# A-Power.net
KiCad netlist of a schematic drawn in Altium Designer
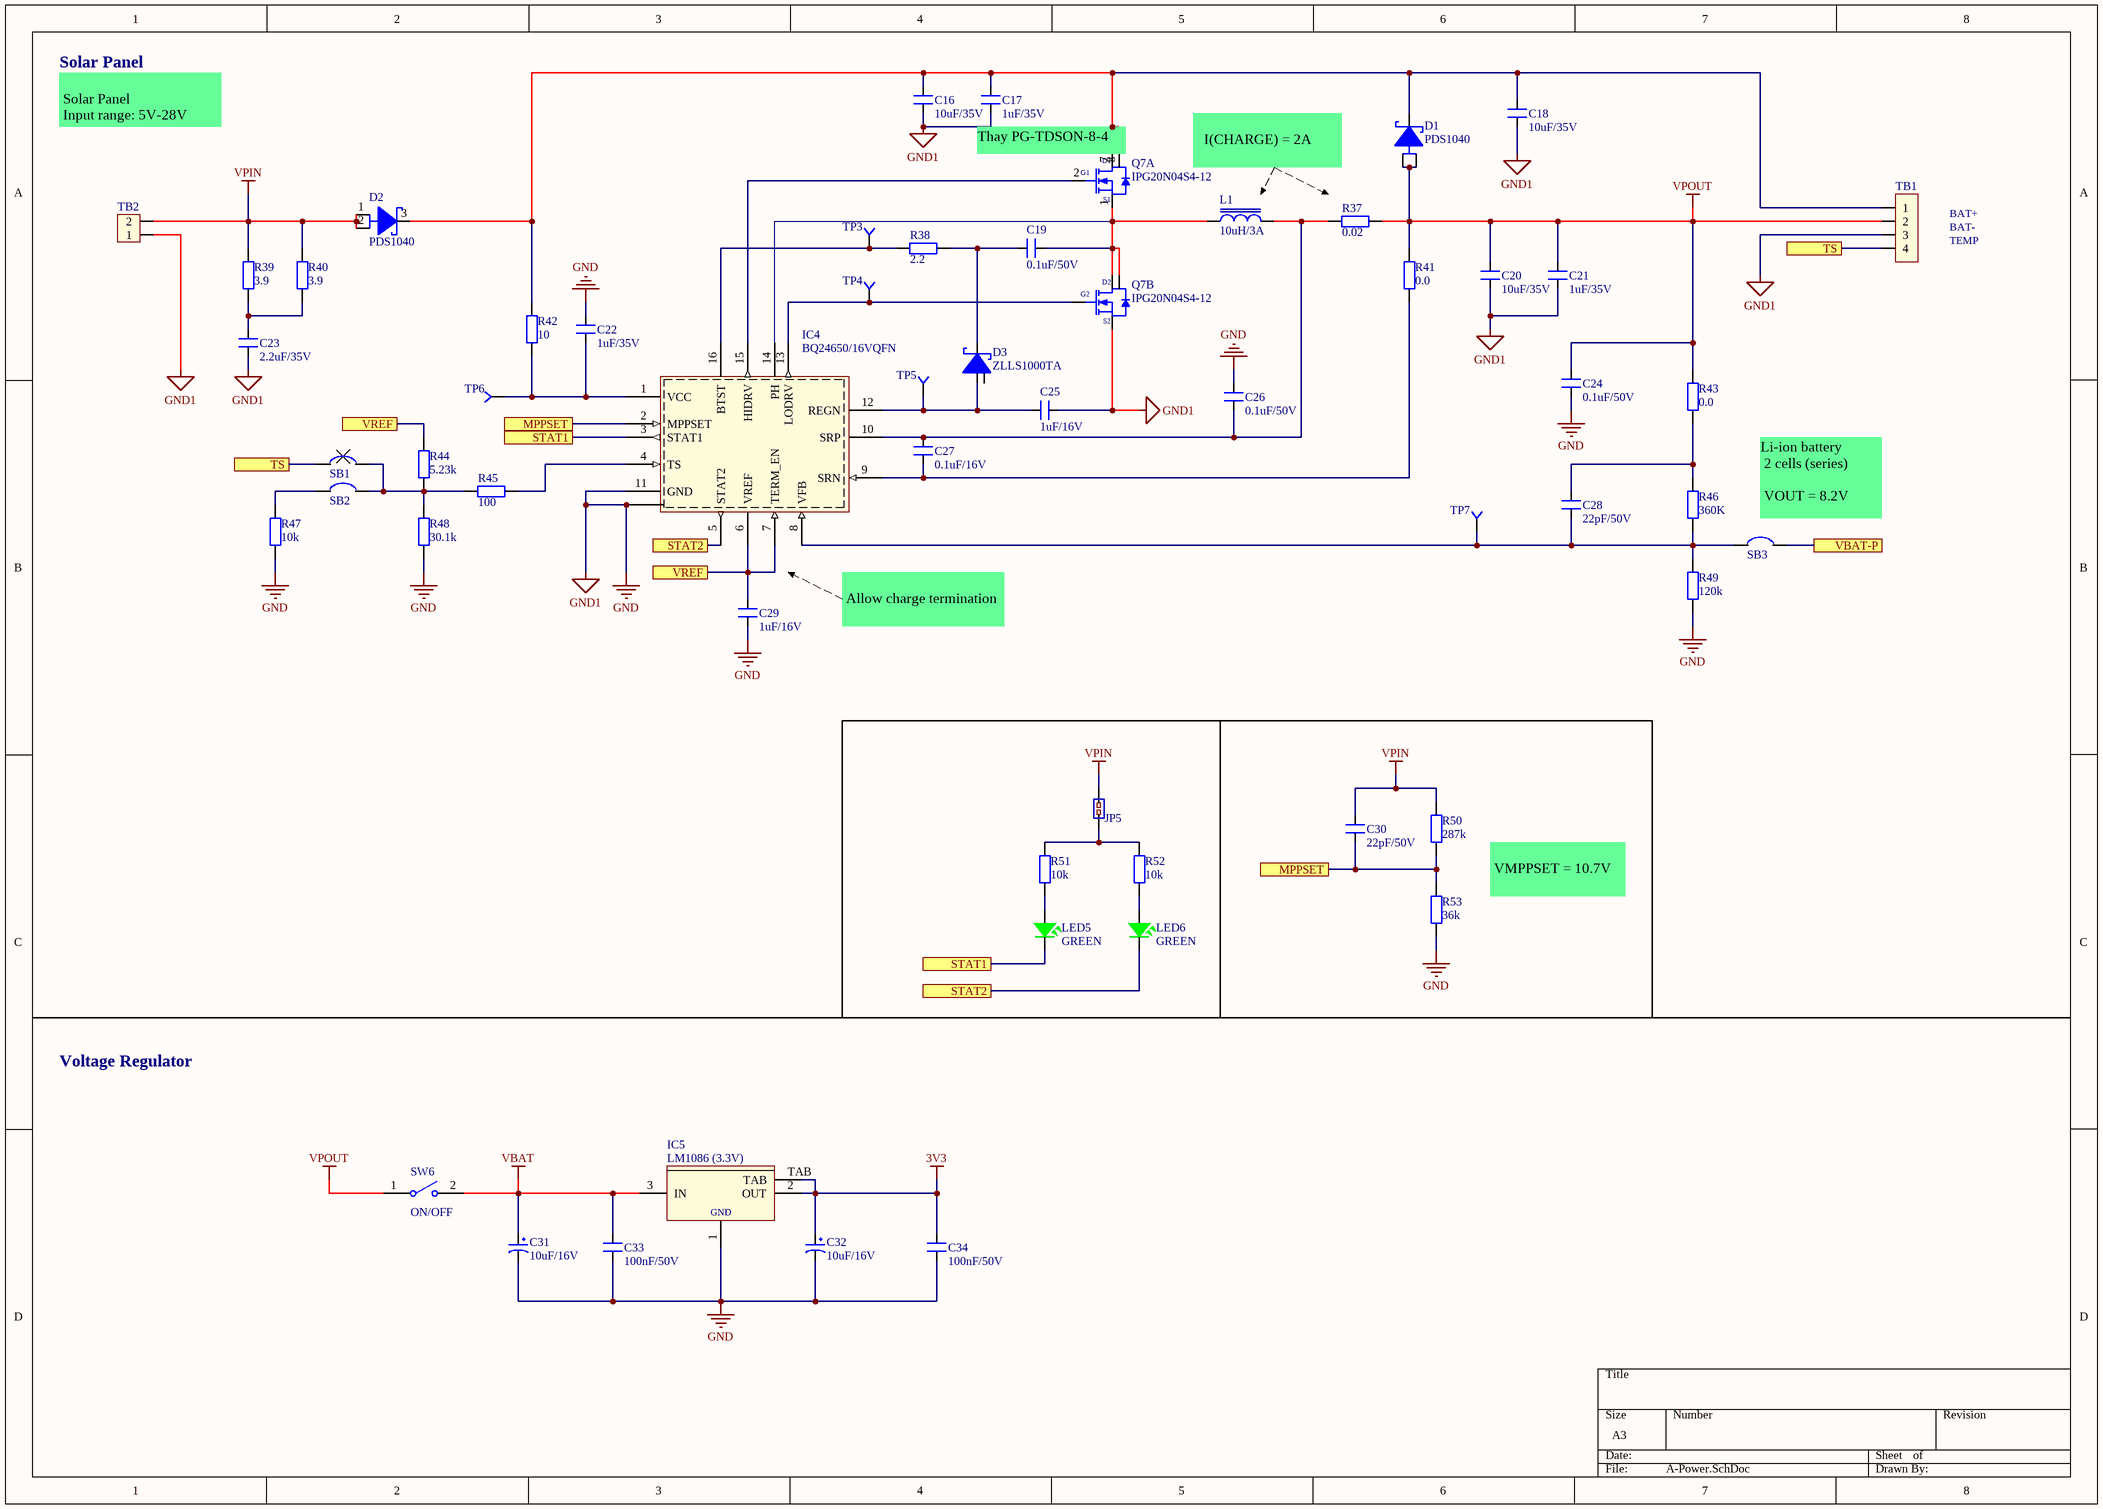
[diagram p0: A-Power.SchDoc]

(export (version "E")
  (design (tool "Eeschema 10.0.6"))
  (components
    (comp (ref "C16")
      (value "10uF/35V")
      (footprint "CAP_CERA_C3216(CC1206INCH)")
      (description "CAP CER 10UF 35V X7R 1206")
      (fields
        (field (name "MANUFACTURER") "Taiyo Yuden")
        (field (name "MANUFACTURER PART NUMBER") "GMK316AB7106KL-TR")
      )
      (libsource (lib "Tran Tuan") (part "CAP-CER/10uF/35V/X7R-1206"))
    )
    (comp (ref "C17")
      (value "1uF/35V")
      (footprint "CAP_CERA_C2012(CC0805INCH)")
      (description "CAP CER 1UF 35V X7R 0805")
      (fields
        (field (name "MANUFACTURER") "Taiyo Yuden")
        (field (name "MANUFACTURER PART NUMBER") "GMK212B7105KG-T")
      )
      (libsource (lib "Tran Tuan") (part "CAP-CER/1uF/35V/X7R/0805"))
    )
    (comp (ref "C18")
      (value "10uF/35V")
      (footprint "CAP_CERA_C3216(CC1206INCH)")
      (description "CAP CER 10UF 35V X7R 1206")
      (fields
        (field (name "MANUFACTURER") "Taiyo Yuden")
        (field (name "MANUFACTURER PART NUMBER") "GMK316AB7106KL-TR")
      )
      (libsource (lib "Tran Tuan") (part "CAP-CER/10uF/35V/X7R-1206"))
    )
    (comp (ref "C19")
      (value "0.1uF/50V")
      (footprint "CAP_CERA_C1608(CC0603INCH)")
      (description "CAP CER 0.1UF 50V X7R 0603")
      (fields
        (field (name "MANUFACTURER") "Kemet")
        (field (name "MANUFACTURER PART NUMBER") "C0603X104K5RACTU")
      )
      (libsource (lib "Tran Tuan") (part "CAP-CER/0.1uF/50V/X7R/0603"))
    )
    (comp (ref "C20")
      (value "10uF/35V")
      (footprint "CAP_CERA_C3216(CC1206INCH)")
      (description "CAP CER 10UF 35V X7R 1206")
      (fields
        (field (name "MANUFACTURER") "Taiyo Yuden")
        (field (name "MANUFACTURER PART NUMBER") "GMK316AB7106KL-TR")
      )
      (libsource (lib "Tran Tuan") (part "CAP-CER/10uF/35V/X7R-1206"))
    )
    (comp (ref "C21")
      (value "1uF/35V")
      (footprint "CAP_CERA_C2012(CC0805INCH)")
      (description "CAP CER 1UF 35V X7R 0805")
      (fields
        (field (name "MANUFACTURER") "Taiyo Yuden")
        (field (name "MANUFACTURER PART NUMBER") "GMK212B7105KG-T")
      )
      (libsource (lib "Tran Tuan") (part "CAP-CER/1uF/35V/X7R/0805"))
    )
    (comp (ref "C22")
      (value "1uF/35V")
      (footprint "CAP_CERA_C2012(CC0805INCH)")
      (description "CAP CER 1UF 35V X7R 0805")
      (fields
        (field (name "MANUFACTURER") "Taiyo Yuden")
        (field (name "MANUFACTURER PART NUMBER") "GMK212B7105KG-T")
      )
      (libsource (lib "Tran Tuan") (part "CAP-CER/1uF/35V/X7R/0805"))
    )
    (comp (ref "C23")
      (value "2.2uF/35V")
      (footprint "CAP_CERA_C3225(CC1210)")
      (description "CAP CER 2.2UF 35V X7R 1210")
      (fields
        (field (name "MANUFACTURER") "Taiyo Yuden")
        (field (name "MANUFACTURER PART NUMBER") "GMK325B7225KNHT")
      )
      (libsource (lib "Tran Tuan") (part "CAP-CER/2.2uF/35V/X7R/1210"))
    )
    (comp (ref "C24")
      (value "0.1uF/50V")
      (footprint "CAP_CERA_C1608(CC0603INCH)")
      (description "CAP CER 0.1UF 50V X7R 0603")
      (fields
        (field (name "MANUFACTURER") "Kemet")
        (field (name "MANUFACTURER PART NUMBER") "C0603X104K5RACTU")
      )
      (libsource (lib "Tran Tuan") (part "CAP-CER/0.1uF/50V/X7R/0603"))
    )
    (comp (ref "C25")
      (value "1uF/16V")
      (footprint "CAP_CERA_C2012(CC0805INCH)")
      (description "CAP CER 1UF 16V X7R 0805")
      (fields
        (field (name "MANUFACTURER") "Kemet")
        (field (name "MANUFACTURER PART NUMBER") "C0805C105K4RACTU")
      )
      (libsource (lib "Tran Tuan") (part "CAP-CER/1uF/16V/X7R/0805"))
    )
    (comp (ref "C26")
      (value "0.1uF/50V")
      (footprint "CAP_CERA_C1608(CC0603INCH)")
      (description "CAP CER 0.1UF 50V X7R 0603")
      (fields
        (field (name "MANUFACTURER") "Kemet")
        (field (name "MANUFACTURER PART NUMBER") "C0603X104K5RACTU")
      )
      (libsource (lib "Tran Tuan") (part "CAP-CER/0.1uF/50V/X7R/0603"))
    )
    (comp (ref "C27")
      (value "0.1uF/16V")
      (footprint "CAP_CERA_C1608(CC0603INCH)")
      (description "CAP CER 0.1UF 16V X7R 0603")
      (fields
        (field (name "MANUFACTURER") "Yageo")
        (field (name "MANUFACTURER PART NUMBER") "CC0603KRX7R7BB104")
      )
      (libsource (lib "Tran Tuan") (part "CAP-CER/0.1uF/16V/X7R/0603"))
    )
    (comp (ref "C28")
      (value "22pF/50V")
      (footprint "CAP_CERA_C1608(CC0603INCH)")
      (description "CAP CER 22PF 50V X7R 0603")
      (fields
        (field (name "MANUFACTURER") "AVX Corporation")
        (field (name "MANUFACTURER PART NUMBER") "06035C220JAT2A")
      )
      (libsource (lib "Tran Tuan") (part "CAP-CER/22pF/50V/X7R/0603"))
    )
    (comp (ref "C29")
      (value "1uF/16V")
      (footprint "CAP_CERA_C2012(CC0805INCH)")
      (description "CAP CER 1UF 16V X7R 0805")
      (fields
        (field (name "MANUFACTURER") "Kemet")
        (field (name "MANUFACTURER PART NUMBER") "C0805C105K4RACTU")
      )
      (libsource (lib "Tran Tuan") (part "CAP-CER/1uF/16V/X7R/0805"))
    )
    (comp (ref "C30")
      (value "22pF/50V")
      (footprint "CAP_CERA_C1608(CC0603INCH)")
      (description "CAP CER 22PF 50V X7R 0603")
      (fields
        (field (name "MANUFACTURER") "AVX Corporation")
        (field (name "MANUFACTURER PART NUMBER") "06035C220JAT2A")
      )
      (libsource (lib "Tran Tuan") (part "CAP-CER/22pF/50V/X7R/0603"))
    )
    (comp (ref "C31")
      (value "10uF/16V")
      (footprint "CAP_CERA_C3216(CC1206INCH)")
      (description "CAP TANT 10UF 16V 10% 1206")
      (fields
        (field (name "MANUFACTURER") "Kemet")
        (field (name "MANUFACTURER PART NUMBER") "T491A106K016AT")
      )
      (libsource (lib "Tran Tuan") (part "CAP-TANT/10uF/16V/1206"))
    )
    (comp (ref "C32")
      (value "10uF/16V")
      (footprint "CAP_CERA_C3216(CC1206INCH)")
      (description "CAP TANT 10UF 16V 10% 1206")
      (fields
        (field (name "MANUFACTURER") "Kemet")
        (field (name "MANUFACTURER PART NUMBER") "T491A106K016AT")
      )
      (libsource (lib "Tran Tuan") (part "CAP-TANT/10uF/16V/1206"))
    )
    (comp (ref "C33")
      (value "100nF/50V")
      (footprint "CAP_CERA_C2012(CC0805INCH)")
      (description "CAP CER 0.1UF 50V X7R 0805")
      (fields
        (field (name "MANUFACTURER") "AVX Corporation")
        (field (name "MANUFACTURER PART NUMBER") "08055C104KAT2A")
      )
      (libsource (lib "Tran Tuan") (part "CAP-CER/100nF/50V/X7R-0805"))
    )
    (comp (ref "C34")
      (value "100nF/50V")
      (footprint "CAP_CERA_C2012(CC0805INCH)")
      (description "CAP CER 0.1UF 50V X7R 0805")
      (fields
        (field (name "MANUFACTURER") "AVX Corporation")
        (field (name "MANUFACTURER PART NUMBER") "08055C104KAT2A")
      )
      (libsource (lib "Tran Tuan") (part "CAP-CER/100nF/50V/X7R-0805"))
    )
    (comp (ref "D1")
      (value "PDS1040")
      (footprint "PDS1040")
      (description "DIODE SCHOTTKY 40V 10A POWERDI5")
      (fields
        (field (name "MANUFACTURER") "Diodes Incorporated")
        (field (name "MANUFACTURER PART NUMBER") "PDS1040-13")
      )
      (libsource (lib "") (part "DIODE-PDS1040/POWERDI5_1"))
    )
    (comp (ref "D2")
      (value "PDS1040")
      (footprint "PDS1040")
      (description "DIODE SCHOTTKY 40V 10A POWERDI5")
      (fields
        (field (name "MANUFACTURER") "Diodes Incorporated")
        (field (name "MANUFACTURER PART NUMBER") "PDS1040-13")
      )
      (libsource (lib "Tran Tuan") (part "DIODE-PDS1040/POWERDI5"))
    )
    (comp (ref "D3")
      (value "ZLLS1000TA")
      (footprint "ZLLS1000")
      (description "DIODE SCHOTTKY 40V 1.16A SOT23-3")
      (fields (field (name "MANUFACTURER") "Diodes Incorporated"))
      (libsource (lib "Tran Tuan") (part "DIODE-ZLLS1000TA/SOT23-3"))
    )
    (comp (ref "IC4")
      (value "BQ24650/16VQFN")
      (footprint "BQ24650-16VQFN")
      (description "IC SYNC SW-MODE BAT CHRGR 16VQFN")
      (fields
        (field (name "MANUFACTURER") "Texas Instruments")
        (field (name "MANUFACTURER PART NUMBER") "BQ24650RVAT")
      )
      (libsource (lib "Tran Tuan") (part "BQ24650/16VQFN"))
    )
    (comp (ref "IC5")
      (value "LM1086 (3.3V)")
      (footprint "LM1086")
      (description "IC REG LDO 3.3V 1.5A DDPAK")
      (fields
        (field (name "MANUFACTURER") "Texas Instruments")
        (field (name "MANUFACTURER PART NUMBER") "LM1086CS-3.3/NOPB")
      )
      (libsource (lib "Tran Tuan") (part "LM1086CS-3.3/NOPB"))
    )
    (comp (ref "JP5")
      (value "JP2-ShortingJumper")
      (footprint "Header_2")
      (description "2.54mm 2-Pin Shorting Jumper")
      (libsource (lib "Tran Tuan") (part "JP2-ShortingJumper"))
    )
    (comp (ref "L1")
      (value "10uH/3A")
      (footprint "IHLP-2525CZ-01")
      (description "FIXED IND 10UH 3A 105mOHM SMD")
      (fields
        (field (name "MANUFACTURER") "Vishay Dale")
        (field (name "MANUFACTURER PART NUMBER") "IHLP2525CZER100M01")
      )
      (libsource (lib "Tran Tuan") (part "IND-10uH/3A/105mOHM"))
    )
    (comp (ref "LED5")
      (value "GREEN")
      (footprint "Led 0805G")
      (description "LED GREEN CLEAR 0805 SMD")
      (fields
        (field (name "MANUFACTURER") "Lite-On Inc.")
        (field (name "MANUFACTURER PART NUMBER") "LTST-C171GKT")
      )
      (libsource (lib "Tran Tuan") (part "LED-GREEN/CLEAR/0805"))
    )
    (comp (ref "LED6")
      (value "GREEN")
      (footprint "Led 0805G")
      (description "LED GREEN CLEAR 0805 SMD")
      (fields
        (field (name "MANUFACTURER") "Lite-On Inc.")
        (field (name "MANUFACTURER PART NUMBER") "LTST-C171GKT")
      )
      (libsource (lib "Tran Tuan") (part "LED-GREEN/CLEAR/0805"))
    )
    (comp (ref "Q7")
      (value "IPG20N04S4-12")
      (footprint "PG-TDSON-8-4")
      (description "MOSFE,T 2N-CH, 40V 20A TDSON-8 OptiMOS-T2")
      (fields (field (name "MANUFACTURER") "Infineon"))
      (libsource (lib "Tran Tuan") (part "MOSFET-IPG20N04S4/TDSON8"))
    )
    (comp (ref "R37")
      (value "~")
      (footprint "RES-1206-3216MM")
      (description "RES SMD 0.02 OHM 1% 1W 1206")
      (fields
        (field (name "MANUFACTURER") "Vishay Dale")
        (field (name "MANUFACTURER PART NUMBER") "WSLP1206R0200FEA")
        (field (name "RESISTANCE (OHMS)") "0.02")
      )
      (libsource (lib "Tran Tuan") (part "RES-1206/±1%"))
    )
    (comp (ref "R38")
      (value "~")
      (footprint "RESC2012(0805)")
      (description "RES SMD 2.2 OHM 5% 1/8W 0805")
      (fields
        (field (name "MANUFACTURER") "Panasonic Electronic Components")
        (field (name "MANUFACTURER PART NUMBER") "ERJ-6GEYJ2R2V")
        (field (name "RESISTANCE (OHMS)") "2.2")
      )
      (libsource (lib "Tran Tuan") (part "RES-0805/±5%"))
    )
    (comp (ref "R39")
      (value "~")
      (footprint "RES-1206-3216MM")
      (description "RES SMD 3.9 OHM 1% 1/4W 1206")
      (fields
        (field (name "MANUFACTURER") "Panasonic Electronic Components")
        (field (name "MANUFACTURER PART NUMBER") "ERJ-8RQF3R9V")
        (field (name "RESISTANCE (OHMS)") "3.9")
      )
      (libsource (lib "Tran Tuan") (part "RES-1206/±5%"))
    )
    (comp (ref "R40")
      (value "~")
      (footprint "RES-1206-3216MM")
      (description "RES SMD 3.9 OHM 1% 1/4W 1206")
      (fields
        (field (name "MANUFACTURER") "Panasonic Electronic Components")
        (field (name "MANUFACTURER PART NUMBER") "ERJ-8RQF3R9V")
        (field (name "RESISTANCE (OHMS)") "3.9")
      )
      (libsource (lib "Tran Tuan") (part "RES-1206/±5%"))
    )
    (comp (ref "R41")
      (value "~")
      (footprint "RESC2012(0805)")
      (description "RES SMD 0.0 OHM JUMPER 1/8W 0805")
      (fields
        (field (name "MANUFACTURER") "Yageo")
        (field (name "MANUFACTURER PART NUMBER") "RC0805JR-070RL")
        (field (name "RESISTANCE (OHMS)") "0.0")
      )
      (libsource (lib "") (part "RES-0805/±5%_1"))
    )
    (comp (ref "R42")
      (value "~")
      (footprint "RESC2012(0805)")
      (description "RES SMD 10 OHM 5% 1/8W 0805")
      (fields
        (field (name "MANUFACTURER") "Yageo")
        (field (name "MANUFACTURER PART NUMBER") "RC0805JR-0710RL")
        (field (name "RESISTANCE (OHMS)") "10")
      )
      (libsource (lib "") (part "RES-0805/±5%_1"))
    )
    (comp (ref "R43")
      (value "~")
      (footprint "RESC2012(0805)")
      (description "RES SMD 0.0 OHM JUMPER 1/8W 0805")
      (fields
        (field (name "MANUFACTURER") "Yageo")
        (field (name "MANUFACTURER PART NUMBER") "RC0805JR-070RL")
        (field (name "RESISTANCE (OHMS)") "0.0")
      )
      (libsource (lib "") (part "RES-0805/±5%_1"))
    )
    (comp (ref "R44")
      (value "~")
      (footprint "RESC2012(0805)")
      (description "RES SMD 5.23K OHM 1% 1/8W 0805")
      (fields
        (field (name "MANUFACTURER") "Panasonic Electronic Components")
        (field (name "MANUFACTURER PART NUMBER") "ERJ-6ENF5231V")
        (field (name "RESISTANCE (OHMS)") "5.23k")
      )
      (libsource (lib "") (part "RES-0805/±1%_1"))
    )
    (comp (ref "R45")
      (value "~")
      (footprint "RESC2012(0805)")
      (description "RES SMD 100 OHM 5% 1/8W 0805")
      (fields
        (field (name "MANUFACTURER") "Panasonic Electronic Components")
        (field (name "MANUFACTURER PART NUMBER") "ERJ-6GEYJ101V")
        (field (name "RESISTANCE (OHMS)") "100")
      )
      (libsource (lib "Tran Tuan") (part "RES-0805/±5%"))
    )
    (comp (ref "R46")
      (value "360K")
      (footprint "RESC2012(0805)")
      (description "RES SMD 360K OHM 1% 1/8W 0805")
      (fields
        (field (name "MANUFACTURER") "Yageo")
        (field (name "MANUFACTURER PART NUMBER") "RC0805FR-07360KL")
      )
      (libsource (lib "Tran Tuan") (part "RES-0805/±1%"))
    )
    (comp (ref "R47")
      (value "~")
      (footprint "RESC2012(0805)")
      (description "RES SMD 10K OHM 5% 1/8W 0805")
      (fields
        (field (name "MANUFACTURER") "Yageo")
        (field (name "MANUFACTURER PART NUMBER") "RC0805JR-0710KL")
        (field (name "RESISTANCE (OHMS)") "10k")
      )
      (libsource (lib "") (part "RES-0805/±5%_1"))
    )
    (comp (ref "R48")
      (value "~")
      (footprint "RESC2012(0805)")
      (description "RES SMD 30.1K OHM 1% 1/8W 0805")
      (fields
        (field (name "MANUFACTURER") "Yageo")
        (field (name "MANUFACTURER PART NUMBER") "RC0805FR-0730K1L")
        (field (name "RESISTANCE (OHMS)") "30.1k")
      )
      (libsource (lib "") (part "RES-0805/±1%_1"))
    )
    (comp (ref "R49")
      (value "~")
      (footprint "RESC2012(0805)")
      (description "RES SMD 120K OHM 1% 1/8W 0805")
      (fields
        (field (name "MANUFACTURER") "Yageo")
        (field (name "MANUFACTURER PART NUMBER") "RC0805FR-07120KL")
        (field (name "RESISTANCE (OHMS)") "120k")
      )
      (libsource (lib "") (part "RES-0805/±1%_1"))
    )
    (comp (ref "R50")
      (value "~")
      (footprint "RESC2012(0805)")
      (description "RES SMD 287K OHM 1% 1/8W 0805")
      (fields
        (field (name "MANUFACTURER") "Panasonic Electronic Components")
        (field (name "MANUFACTURER PART NUMBER") "ERJ-6ENF2873V")
        (field (name "RESISTANCE (OHMS)") "287k")
      )
      (libsource (lib "") (part "RES-0805/±1%_1"))
    )
    (comp (ref "R51")
      (value "~")
      (footprint "RESC2012(0805)")
      (description "RES SMD 10K OHM 5% 1/8W 0805")
      (fields
        (field (name "MANUFACTURER") "Yageo")
        (field (name "MANUFACTURER PART NUMBER") "RC0805JR-0710KL")
        (field (name "RESISTANCE (OHMS)") "10k")
      )
      (libsource (lib "") (part "RES-0805/±5%_1"))
    )
    (comp (ref "R52")
      (value "~")
      (footprint "RESC2012(0805)")
      (description "RES SMD 10K OHM 5% 1/8W 0805")
      (fields
        (field (name "MANUFACTURER") "Yageo")
        (field (name "MANUFACTURER PART NUMBER") "RC0805JR-0710KL")
        (field (name "RESISTANCE (OHMS)") "10k")
      )
      (libsource (lib "") (part "RES-0805/±5%_1"))
    )
    (comp (ref "R53")
      (value "~")
      (footprint "RESC2012(0805)")
      (description "RES SMD 36K OHM 1% 1/8W 0805")
      (fields
        (field (name "MANUFACTURER") "Panasonic Electronic Components")
        (field (name "MANUFACTURER PART NUMBER") "ERJ-6ENF3602V")
        (field (name "RESISTANCE (OHMS)") "36k")
      )
      (libsource (lib "Tran Tuan") (part "RES-0805/±1%"))
    )
    (comp (ref "SB1")
      (value "Not connect")
      (footprint "head PAD")
      (description "Jumper, Connector, 2-pad")
      (libsource (lib "Tran Tuan") (part "Connector-NSB"))
    )
    (comp (ref "SB2")
      (value "Connect")
      (footprint "head PAD")
      (description "Jumper, Connector, 2-pad")
      (libsource (lib "Tran Tuan") (part "Connector-SB"))
    )
    (comp (ref "SB3")
      (value "Connect")
      (footprint "head PAD")
      (description "Jumper, Connector, 2-pad")
      (libsource (lib "Tran Tuan") (part "Connector-SB"))
    )
    (comp (ref "SW6")
      (value "ON/OFF")
      (footprint "SW-POWER")
      (description "SWITCH ROCKER SPST 16A 125V")
      (fields
        (field (name "MANUFACTURER") "TE Connectivity Alcoswitch Switches")
        (field (name "MANUFACTURER PART NUMBER") "PRASA1-16F-BB0BW")
      )
      (libsource (lib "Tran Tuan") (part "SW-ROCKER/SPST/16A"))
    )
    (comp (ref "TB1")
      (value "TERM BLOCK")
      (footprint "MKDS-DOMINO-4-PIN")
      (description "TERM BLOCK 4POS 3.81MM PCB GRN")
      (fields
        (field (name "MANUFACTURER") "Phoenix Contact")
        (field (name "MANUFACTURER PART NUMBER") "1727036")
      )
      (libsource (lib "Tran Tuan") (part "TERM/3.81MM/4POS/GREEN"))
    )
    (comp (ref "TB2")
      (value "TERM BLOCK")
      (footprint "MKDS-DOMINO-2-PIN")
      (description "TERM BLOCK 2POS 3.81MM PCB GRN")
      (fields
        (field (name "MANUFACTURER") "Phoenix Contact")
        (field (name "MANUFACTURER PART NUMBER") "1727010")
      )
      (libsource (lib "Tran Tuan") (part "TERM/3.81MM/2POS/GREEN"))
    )
    (comp (ref "TP3")
      (value "Test Point")
      (footprint "Test_point_VIA06")
      (description "Test Point, Pad, Hole")
      (libsource (lib "Tran Tuan") (part "Connector-TP"))
    )
    (comp (ref "TP4")
      (value "Test Point")
      (footprint "Test_point_VIA06")
      (description "Test Point, Pad, Hole")
      (libsource (lib "Tran Tuan") (part "Connector-TP"))
    )
    (comp (ref "TP5")
      (value "Test Point")
      (footprint "Test_point_VIA06")
      (description "Test Point, Pad, Hole")
      (libsource (lib "Tran Tuan") (part "Connector-TP"))
    )
    (comp (ref "TP6")
      (value "Test Point")
      (footprint "Test_point_VIA06")
      (description "Test Point, Pad, Hole")
      (libsource (lib "Tran Tuan") (part "Connector-TP"))
    )
    (comp (ref "TP7")
      (value "Test Point")
      (footprint "Test_point_VIA06")
      (description "Test Point, Pad, Hole")
      (libsource (lib "Tran Tuan") (part "Connector-TP"))
    )
  )
  (nets
    (net (code "1") (name "/MPPSET") (class "Default")
      (node (ref "C30") (pin "2") (pinfunction "2_2") (pintype "passive"))
      (node (ref "IC4") (pin "2") (pinfunction "MPPSET_2") (pintype "input"))
      (node (ref "R50") (pin "2") (pinfunction "2_2") (pintype "passive"))
      (node (ref "R53") (pin "2") (pinfunction "2_2") (pintype "passive"))
    )
    (net (code "2") (name "/STAT1") (class "Default")
      (node (ref "IC4") (pin "3") (pinfunction "STAT1_3") (pintype "output"))
      (node (ref "LED5") (pin "2") (pinfunction "K_2") (pintype "passive"))
    )
    (net (code "3") (name "/STAT2") (class "Default")
      (node (ref "IC4") (pin "5") (pinfunction "STAT2_5") (pintype "output"))
      (node (ref "LED6") (pin "2") (pinfunction "K_2") (pintype "passive"))
    )
    (net (code "4") (name "/TS") (class "Default")
      (node (ref "SB1") (pin "2") (pinfunction "2_2") (pintype "passive"))
      (node (ref "TB1") (pin "4") (pinfunction "4_4") (pintype "passive"))
    )
    (net (code "5") (name "/VBAT-P") (class "Default")
      (node (ref "SB3") (pin "1") (pinfunction "1_1") (pintype "passive"))
    )
    (net (code "6") (name "/VREF") (class "Default")
      (node (ref "C29") (pin "2") (pinfunction "2_2") (pintype "passive"))
      (node (ref "IC4") (pin "6") (pinfunction "VREF_6") (pintype "power_in"))
      (node (ref "IC4") (pin "7") (pinfunction "TERM_EN_7") (pintype "input"))
      (node (ref "R44") (pin "1") (pinfunction "1_1") (pintype "passive"))
    )
    (net (code "7") (name "3V3") (class "Default")
      (node (ref "C32") (pin "1") (pinfunction "1_1") (pintype "passive"))
      (node (ref "C34") (pin "1") (pinfunction "1_1") (pintype "passive"))
      (node (ref "IC5") (pin "2") (pinfunction "OUT_2") (pintype "power_in"))
      (node (ref "IC5") (pin "TAB") (pinfunction "TAB_TAB") (pintype "power_in"))
    )
    (net (code "8") (name "GND") (class "Default")
      (node (ref "C16") (pin "2") (pinfunction "2_2") (pintype "passive"))
      (node (ref "C17") (pin "2") (pinfunction "2_2") (pintype "passive"))
      (node (ref "C18") (pin "2") (pinfunction "2_2") (pintype "passive"))
      (node (ref "C20") (pin "2") (pinfunction "2_2") (pintype "passive"))
      (node (ref "C21") (pin "2") (pinfunction "2_2") (pintype "passive"))
      (node (ref "C22") (pin "2") (pinfunction "2_2") (pintype "passive"))
      (node (ref "C23") (pin "2") (pinfunction "2_2") (pintype "passive"))
      (node (ref "C24") (pin "1") (pinfunction "1_1") (pintype "passive"))
      (node (ref "C25") (pin "1") (pinfunction "1_1") (pintype "passive"))
      (node (ref "C26") (pin "2") (pinfunction "2_2") (pintype "passive"))
      (node (ref "C29") (pin "1") (pinfunction "1_1") (pintype "passive"))
      (node (ref "C31") (pin "2") (pinfunction "2_2") (pintype "passive"))
      (node (ref "C32") (pin "2") (pinfunction "2_2") (pintype "passive"))
      (node (ref "C33") (pin "2") (pinfunction "2_2") (pintype "passive"))
      (node (ref "C34") (pin "2") (pinfunction "2_2") (pintype "passive"))
      (node (ref "IC4") (pin "11") (pinfunction "GND_11") (pintype "power_in"))
      (node (ref "IC4") (pin "PAD") (pinfunction "PAD_PAD") (pintype "power_in"))
      (node (ref "IC5") (pin "1") (pinfunction "GND_1") (pintype "power_in"))
      (node (ref "Q7") (pin "3") (pinfunction "S2_3") (pintype "passive"))
      (node (ref "R47") (pin "2") (pinfunction "2_2") (pintype "passive"))
      (node (ref "R48") (pin "2") (pinfunction "2_2") (pintype "passive"))
      (node (ref "R49") (pin "2") (pinfunction "2_2") (pintype "passive"))
      (node (ref "R53") (pin "1") (pinfunction "1_1") (pintype "passive"))
      (node (ref "TB1") (pin "3") (pinfunction "3_3") (pintype "passive"))
      (node (ref "TB2") (pin "1") (pinfunction "1_1") (pintype "passive"))
    )
    (net (code "9") (name "Net-(C23-Pad1)") (class "Default")
      (node (ref "C23") (pin "1") (pinfunction "1_1") (pintype "passive"))
      (node (ref "R39") (pin "2") (pinfunction "2_2") (pintype "passive"))
      (node (ref "R40") (pin "2") (pinfunction "2_2") (pintype "passive"))
    )
    (net (code "10") (name "Net-(C28-Pad1)") (class "Default")
      (node (ref "C28") (pin "1") (pinfunction "1_1") (pintype "passive"))
      (node (ref "R43") (pin "2") (pinfunction "2_2") (pintype "passive"))
      (node (ref "R46") (pin "2") (pinfunction "2_2") (pintype "passive"))
    )
    (net (code "11") (name "Net-(D1-K)") (class "Default")
      (node (ref "C16") (pin "1") (pinfunction "1_1") (pintype "passive"))
      (node (ref "C17") (pin "1") (pinfunction "1_1") (pintype "passive"))
      (node (ref "C18") (pin "1") (pinfunction "1_1") (pintype "passive"))
      (node (ref "D1") (pin "3") (pinfunction "K_3") (pintype "passive"))
      (node (ref "D2") (pin "3") (pinfunction "K_3") (pintype "passive"))
      (node (ref "Q7") (pin "7") (pinfunction "D1_7") (pintype "passive"))
      (node (ref "Q7") (pin "8") (pinfunction "D1_8") (pintype "passive"))
      (node (ref "R42") (pin "1") (pinfunction "1_1") (pintype "passive"))
      (node (ref "TB1") (pin "1") (pinfunction "1_1") (pintype "passive"))
    )
    (net (code "12") (name "Net-(D3-A)") (class "Default")
      (node (ref "C25") (pin "2") (pinfunction "2_2") (pintype "passive"))
      (node (ref "D3") (pin "1") (pinfunction "A_1") (pintype "passive"))
      (node (ref "IC4") (pin "12") (pinfunction "REGN_12") (pintype "power_in"))
      (node (ref "TP5") (pin "1") (pinfunction "1_1") (pintype "passive"))
    )
    (net (code "13") (name "Net-(D3-K)") (class "Default")
      (node (ref "C19") (pin "1") (pinfunction "1_1") (pintype "passive"))
      (node (ref "D3") (pin "2") (pinfunction "K_2") (pintype "passive"))
      (node (ref "R38") (pin "2") (pinfunction "2_2") (pintype "passive"))
    )
    (net (code "14") (name "Net-(IC4-BTST)") (class "Default")
      (node (ref "IC4") (pin "16") (pinfunction "BTST_16") (pintype "power_in"))
      (node (ref "R38") (pin "1") (pinfunction "1_1") (pintype "passive"))
      (node (ref "TP3") (pin "1") (pinfunction "1_1") (pintype "passive"))
    )
    (net (code "15") (name "Net-(IC4-HIDRV)") (class "Default")
      (node (ref "IC4") (pin "15") (pinfunction "HIDRV_15") (pintype "output"))
      (node (ref "Q7") (pin "2") (pinfunction "G1_2") (pintype "passive"))
    )
    (net (code "16") (name "Net-(IC4-LODRV)") (class "Default")
      (node (ref "IC4") (pin "13") (pinfunction "LODRV_13") (pintype "output"))
      (node (ref "Q7") (pin "4") (pinfunction "G2_4") (pintype "passive"))
      (node (ref "TP4") (pin "1") (pinfunction "1_1") (pintype "passive"))
    )
    (net (code "17") (name "Net-(IC4-PH)") (class "Default")
      (node (ref "C19") (pin "2") (pinfunction "2_2") (pintype "passive"))
      (node (ref "IC4") (pin "14") (pinfunction "PH_14") (pintype "power_in"))
      (node (ref "L1") (pin "1") (pinfunction "1_1") (pintype "passive"))
      (node (ref "Q7") (pin "1") (pinfunction "S1_1") (pintype "passive"))
      (node (ref "Q7") (pin "5") (pinfunction "D2_5") (pintype "passive"))
      (node (ref "Q7") (pin "6") (pinfunction "D2_6") (pintype "passive"))
    )
    (net (code "18") (name "Net-(IC4-SRN)") (class "Default")
      (node (ref "C27") (pin "2") (pinfunction "2_2") (pintype "passive"))
      (node (ref "IC4") (pin "9") (pinfunction "SRN_9") (pintype "input"))
      (node (ref "R41") (pin "2") (pinfunction "2_2") (pintype "passive"))
    )
    (net (code "19") (name "Net-(IC4-SRP)") (class "Default")
      (node (ref "C26") (pin "1") (pinfunction "1_1") (pintype "passive"))
      (node (ref "C27") (pin "1") (pinfunction "1_1") (pintype "passive"))
      (node (ref "IC4") (pin "10") (pinfunction "SRP_10") (pintype "passive"))
      (node (ref "L1") (pin "2") (pinfunction "2_2") (pintype "passive"))
      (node (ref "R37") (pin "1") (pinfunction "1_1") (pintype "passive"))
    )
    (net (code "20") (name "Net-(IC4-TS)") (class "Default")
      (node (ref "IC4") (pin "4") (pinfunction "TS_4") (pintype "input"))
      (node (ref "R45") (pin "2") (pinfunction "2_2") (pintype "passive"))
    )
    (net (code "21") (name "Net-(IC4-VCC)") (class "Default")
      (node (ref "C22") (pin "1") (pinfunction "1_1") (pintype "passive"))
      (node (ref "IC4") (pin "1") (pinfunction "VCC_1") (pintype "power_in"))
      (node (ref "R42") (pin "2") (pinfunction "2_2") (pintype "passive"))
      (node (ref "TP6") (pin "1") (pinfunction "1_1") (pintype "passive"))
    )
    (net (code "22") (name "Net-(IC4-VFB)") (class "Default")
      (node (ref "C28") (pin "2") (pinfunction "2_2") (pintype "passive"))
      (node (ref "IC4") (pin "8") (pinfunction "VFB_8") (pintype "input"))
      (node (ref "R46") (pin "1") (pinfunction "1_1") (pintype "passive"))
      (node (ref "R49") (pin "1") (pinfunction "1_1") (pintype "passive"))
      (node (ref "SB3") (pin "2") (pinfunction "2_2") (pintype "passive"))
      (node (ref "TP7") (pin "1") (pinfunction "1_1") (pintype "passive"))
    )
    (net (code "23") (name "Net-(JP5-Pad1)") (class "Default")
      (node (ref "JP5") (pin "1") (pinfunction "1_1") (pintype "passive"))
      (node (ref "R51") (pin "1") (pinfunction "1_1") (pintype "passive"))
      (node (ref "R52") (pin "1") (pinfunction "1_1") (pintype "passive"))
    )
    (net (code "24") (name "Net-(LED5-A)") (class "Default")
      (node (ref "LED5") (pin "1") (pinfunction "A_1") (pintype "passive"))
      (node (ref "R51") (pin "2") (pinfunction "2_2") (pintype "passive"))
    )
    (net (code "25") (name "Net-(LED6-A)") (class "Default")
      (node (ref "LED6") (pin "1") (pinfunction "A_1") (pintype "passive"))
      (node (ref "R52") (pin "2") (pinfunction "2_2") (pintype "passive"))
    )
    (net (code "26") (name "Net-(R44-Pad2)") (class "Default")
      (node (ref "R44") (pin "2") (pinfunction "2_2") (pintype "passive"))
      (node (ref "R45") (pin "1") (pinfunction "1_1") (pintype "passive"))
      (node (ref "R48") (pin "1") (pinfunction "1_1") (pintype "passive"))
      (node (ref "SB1") (pin "1") (pinfunction "1_1") (pintype "passive"))
      (node (ref "SB2") (pin "1") (pinfunction "1_1") (pintype "passive"))
    )
    (net (code "27") (name "Net-(R47-Pad1)") (class "Default")
      (node (ref "R47") (pin "1") (pinfunction "1_1") (pintype "passive"))
      (node (ref "SB2") (pin "2") (pinfunction "2_2") (pintype "passive"))
    )
    (net (code "28") (name "VBAT") (class "Default")
      (node (ref "C31") (pin "1") (pinfunction "1_1") (pintype "passive"))
      (node (ref "C33") (pin "1") (pinfunction "1_1") (pintype "passive"))
      (node (ref "IC5") (pin "3") (pinfunction "IN_3") (pintype "power_in"))
      (node (ref "SW6") (pin "2") (pinfunction "2_2") (pintype "passive"))
    )
    (net (code "29") (name "VPIN") (class "Default")
      (node (ref "C30") (pin "1") (pinfunction "1_1") (pintype "passive"))
      (node (ref "D2") (pin "1") (pinfunction "A1_1") (pintype "passive"))
      (node (ref "D2") (pin "2") (pinfunction "A2_2") (pintype "passive"))
      (node (ref "JP5") (pin "2") (pinfunction "2_2") (pintype "passive"))
      (node (ref "R39") (pin "1") (pinfunction "1_1") (pintype "passive"))
      (node (ref "R40") (pin "1") (pinfunction "1_1") (pintype "passive"))
      (node (ref "R50") (pin "1") (pinfunction "1_1") (pintype "passive"))
      (node (ref "TB2") (pin "2") (pinfunction "2_2") (pintype "passive"))
    )
    (net (code "30") (name "VPOUT") (class "Default")
      (node (ref "C20") (pin "1") (pinfunction "1_1") (pintype "passive"))
      (node (ref "C21") (pin "1") (pinfunction "1_1") (pintype "passive"))
      (node (ref "C24") (pin "2") (pinfunction "2_2") (pintype "passive"))
      (node (ref "D1") (pin "1") (pinfunction "A1_1") (pintype "passive"))
      (node (ref "D1") (pin "2") (pinfunction "A2_2") (pintype "passive"))
      (node (ref "R37") (pin "2") (pinfunction "2_2") (pintype "passive"))
      (node (ref "R41") (pin "1") (pinfunction "1_1") (pintype "passive"))
      (node (ref "R43") (pin "1") (pinfunction "1_1") (pintype "passive"))
      (node (ref "SW6") (pin "1") (pinfunction "1_1") (pintype "passive"))
      (node (ref "TB1") (pin "2") (pinfunction "2_2") (pintype "passive"))
    )
    (net (code "31") (name "unconnected-(D3-PadNC)") (class "Default")
      (node (ref "D3") (pin "NC") (pinfunction "NC_NC") (pintype "tri_state"))
    )
  )
)
